# 4_5VLDO.net
KiCad netlist of a schematic drawn in Altium Designer
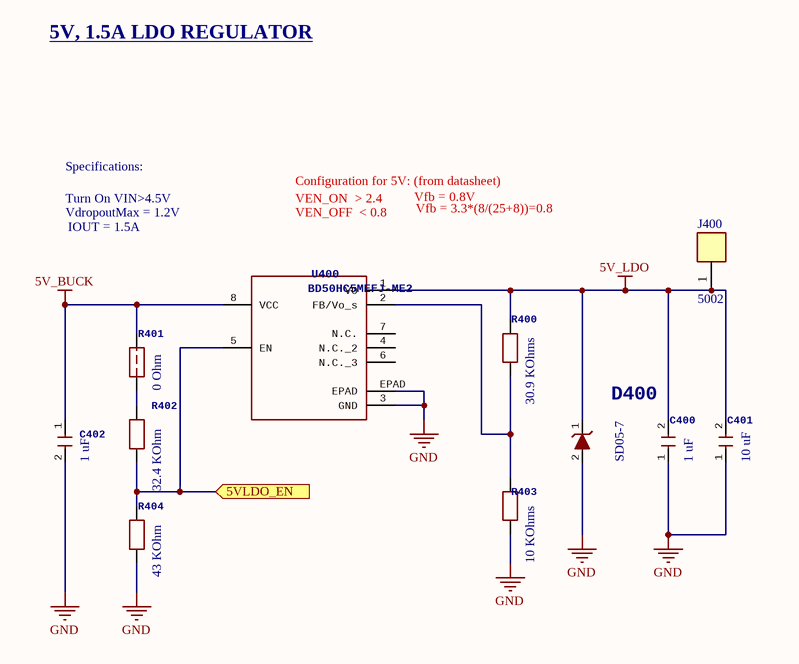
[diagram p0: 4_5VLDO.SchDoc]

(export (version "E")
  (design (tool "Eeschema 10.0.6"))
  (components
    (comp (ref "C400")
      (value "1 uF")
      (footprint "CAP_0603")
      (description "Cap Ceramic 1uF 16V 0603")
      (fields
        (field (name "MANUFACTURER_PART_NUMBER") "GCM188R71C105KA64D")
        (field (name "MOUSER_PART_NUMBER") "81-GCM188R71C105K64D")
      )
      (libsource (lib "Passives") (part "GCM188R71C105KA64D"))
    )
    (comp (ref "C401")
      (value "10 uF")
      (footprint "CAP_0603")
      (description "Cap Ceramic 10uF 35V 0603")
      (fields (field (name "PARTNUMBER") "GRM188R61E106KA73D"))
      (libsource (lib "Passives") (part "GRM188R61E106KA73D"))
    )
    (comp (ref "C402")
      (value "1 uF")
      (footprint "CAP_0603")
      (description "Cap Ceramic 1uF 50V 0603")
      (fields
        (field (name "MANUFACTURER") "Murata Electronics")
        (field (name "PARTNUMBER") "GCM188R71C105KA64")
      )
      (libsource (lib "Passives") (part "GRT188R61H105KE13D"))
    )
    (comp (ref "D400")
      (value "SD05-7")
      (footprint "DIODE_DO-214AC")
      (description "Diode TVS 5V")
      (libsource (lib "Passives") (part "SD05-7"))
    )
    (comp (ref "J400")
      (value "5002")
      (footprint "Miscellaneous:KEYSTONE_5002")
      (description "Test Point Ring Keystone")
      (fields (field (name "MANUFACTURER") "Keystone Electronics"))
      (libsource (lib "Miscellaneous") (part "5002"))
    )
    (comp (ref "R400")
      (value "30.9 KOhms")
      (footprint "RES_0603")
      (description "Res 30.9KOhms 1/8W 0603")
      (fields (field (name "PARTNUMBER") "ERJ6ENF3092V"))
      (libsource (lib "Passives") (part "ERJ6ENF3092V"))
    )
    (comp (ref "R401")
      (value "0 Ohm")
      (footprint "RES_0603")
      (description "Res 0Ohm 1/10W 0603")
      (fields (field (name "PARTNUMBER") "ERJ3GEY0R00V"))
      (libsource (lib "Passives") (part "ERJ3GEY0R00V"))
    )
    (comp (ref "R402")
      (value "32.4 KOhm")
      (footprint "RES_0603")
      (description "Res 32.4KOhm 1/10W 0603")
      (fields (field (name "PARTNUMBER") "RC0603FR-0732K4L"))
      (libsource (lib "Passives") (part "RC0603FR-0732K4L"))
    )
    (comp (ref "R403")
      (value "10 KOhms")
      (footprint "RES_0603")
      (description "Res 10KOhms 1/10W 0603")
      (fields (field (name "PARTNUMBER") "ERJ3GEYJ103V"))
      (libsource (lib "Passives") (part "ERJ3GEYJ103V"))
    )
    (comp (ref "R404")
      (value "43 KOhm")
      (footprint "RES_0603")
      (description "Res 43KOhm 1/10W 0603")
      (fields (field (name "PARTNUMBER") "ERJ3GEYJ433V"))
      (libsource (lib "Passives") (part "ERJ3GEYJ433V"))
    )
    (comp (ref "U400")
      (value "BD50HC5MEFJ-ME2")
      (footprint "REG_SOP8_SOIC8_EPAD")
      (description "LDO 8Vin 5Vout 1.5A")
      (fields (field (name "MANUFACTURER") "ROHM Semiconductor"))
      (libsource (lib "Regulators") (part "BD50HC5MEFJ-ME2"))
    )
  )
  (nets
    (net (code "1") (name "/5VLDO_EN") (class "Default")
      (node (ref "R402") (pin "2") (pinfunction "2_2") (pintype "passive"))
      (node (ref "R404") (pin "2") (pinfunction "2_2") (pintype "passive"))
      (node (ref "U400") (pin "5") (pinfunction "EN_5") (pintype "passive"))
    )
    (net (code "2") (name "5V_BUCK") (class "Default")
      (node (ref "C402") (pin "1") (pinfunction "1_1") (pintype "passive"))
      (node (ref "R401") (pin "2") (pinfunction "2_2") (pintype "passive"))
      (node (ref "U400") (pin "8") (pinfunction "VCC_8") (pintype "power_in"))
    )
    (net (code "3") (name "5V_LDO") (class "Default")
      (node (ref "C400") (pin "2") (pinfunction "2_2") (pintype "passive"))
      (node (ref "C401") (pin "2") (pinfunction "2_2") (pintype "passive"))
      (node (ref "D400") (pin "1") (pinfunction "1_1") (pintype "passive"))
      (node (ref "J400") (pin "1") (pintype "passive"))
      (node (ref "R400") (pin "2") (pinfunction "2_2") (pintype "passive"))
      (node (ref "U400") (pin "1") (pinfunction "VO_1") (pintype "passive"))
    )
    (net (code "4") (name "GND") (class "Default")
      (node (ref "C400") (pin "1") (pinfunction "1_1") (pintype "passive"))
      (node (ref "C401") (pin "1") (pinfunction "1_1") (pintype "passive"))
      (node (ref "C402") (pin "2") (pinfunction "2_2") (pintype "passive"))
      (node (ref "D400") (pin "2") (pinfunction "2_2") (pintype "passive"))
      (node (ref "R403") (pin "1") (pinfunction "1_1") (pintype "passive"))
      (node (ref "R404") (pin "1") (pinfunction "1_1") (pintype "passive"))
      (node (ref "U400") (pin "3") (pinfunction "GND_3") (pintype "passive"))
      (node (ref "U400") (pin "EPAD") (pinfunction "EPAD_EPAD") (pintype "passive"))
    )
    (net (code "5") (name "Net-(R401-Pad1)") (class "Default")
      (node (ref "R401") (pin "1") (pinfunction "1_1") (pintype "passive"))
      (node (ref "R402") (pin "1") (pinfunction "1_1") (pintype "passive"))
    )
    (net (code "6") (name "Net-(U400-FB{slash}Vo_s)") (class "Default")
      (node (ref "R400") (pin "1") (pinfunction "1_1") (pintype "passive"))
      (node (ref "R403") (pin "2") (pinfunction "2_2") (pintype "passive"))
      (node (ref "U400") (pin "2") (pinfunction "FB/Vo_s_2") (pintype "passive"))
    )
    (net (code "7") (name "unconnected-(U400-N.C.-Pad7)") (class "Default")
      (node (ref "U400") (pin "7") (pinfunction "N.C._7") (pintype "passive"))
    )
    (net (code "8") (name "unconnected-(U400-N.C._2-Pad4)") (class "Default")
      (node (ref "U400") (pin "4") (pinfunction "N.C._2_4") (pintype "passive"))
    )
    (net (code "9") (name "unconnected-(U400-N.C._3-Pad6)") (class "Default")
      (node (ref "U400") (pin "6") (pinfunction "N.C._3_6") (pintype "passive"))
    )
  )
)
